# esquematico_drone.net
KiCad netlist of a schematic drawn in EAGLE
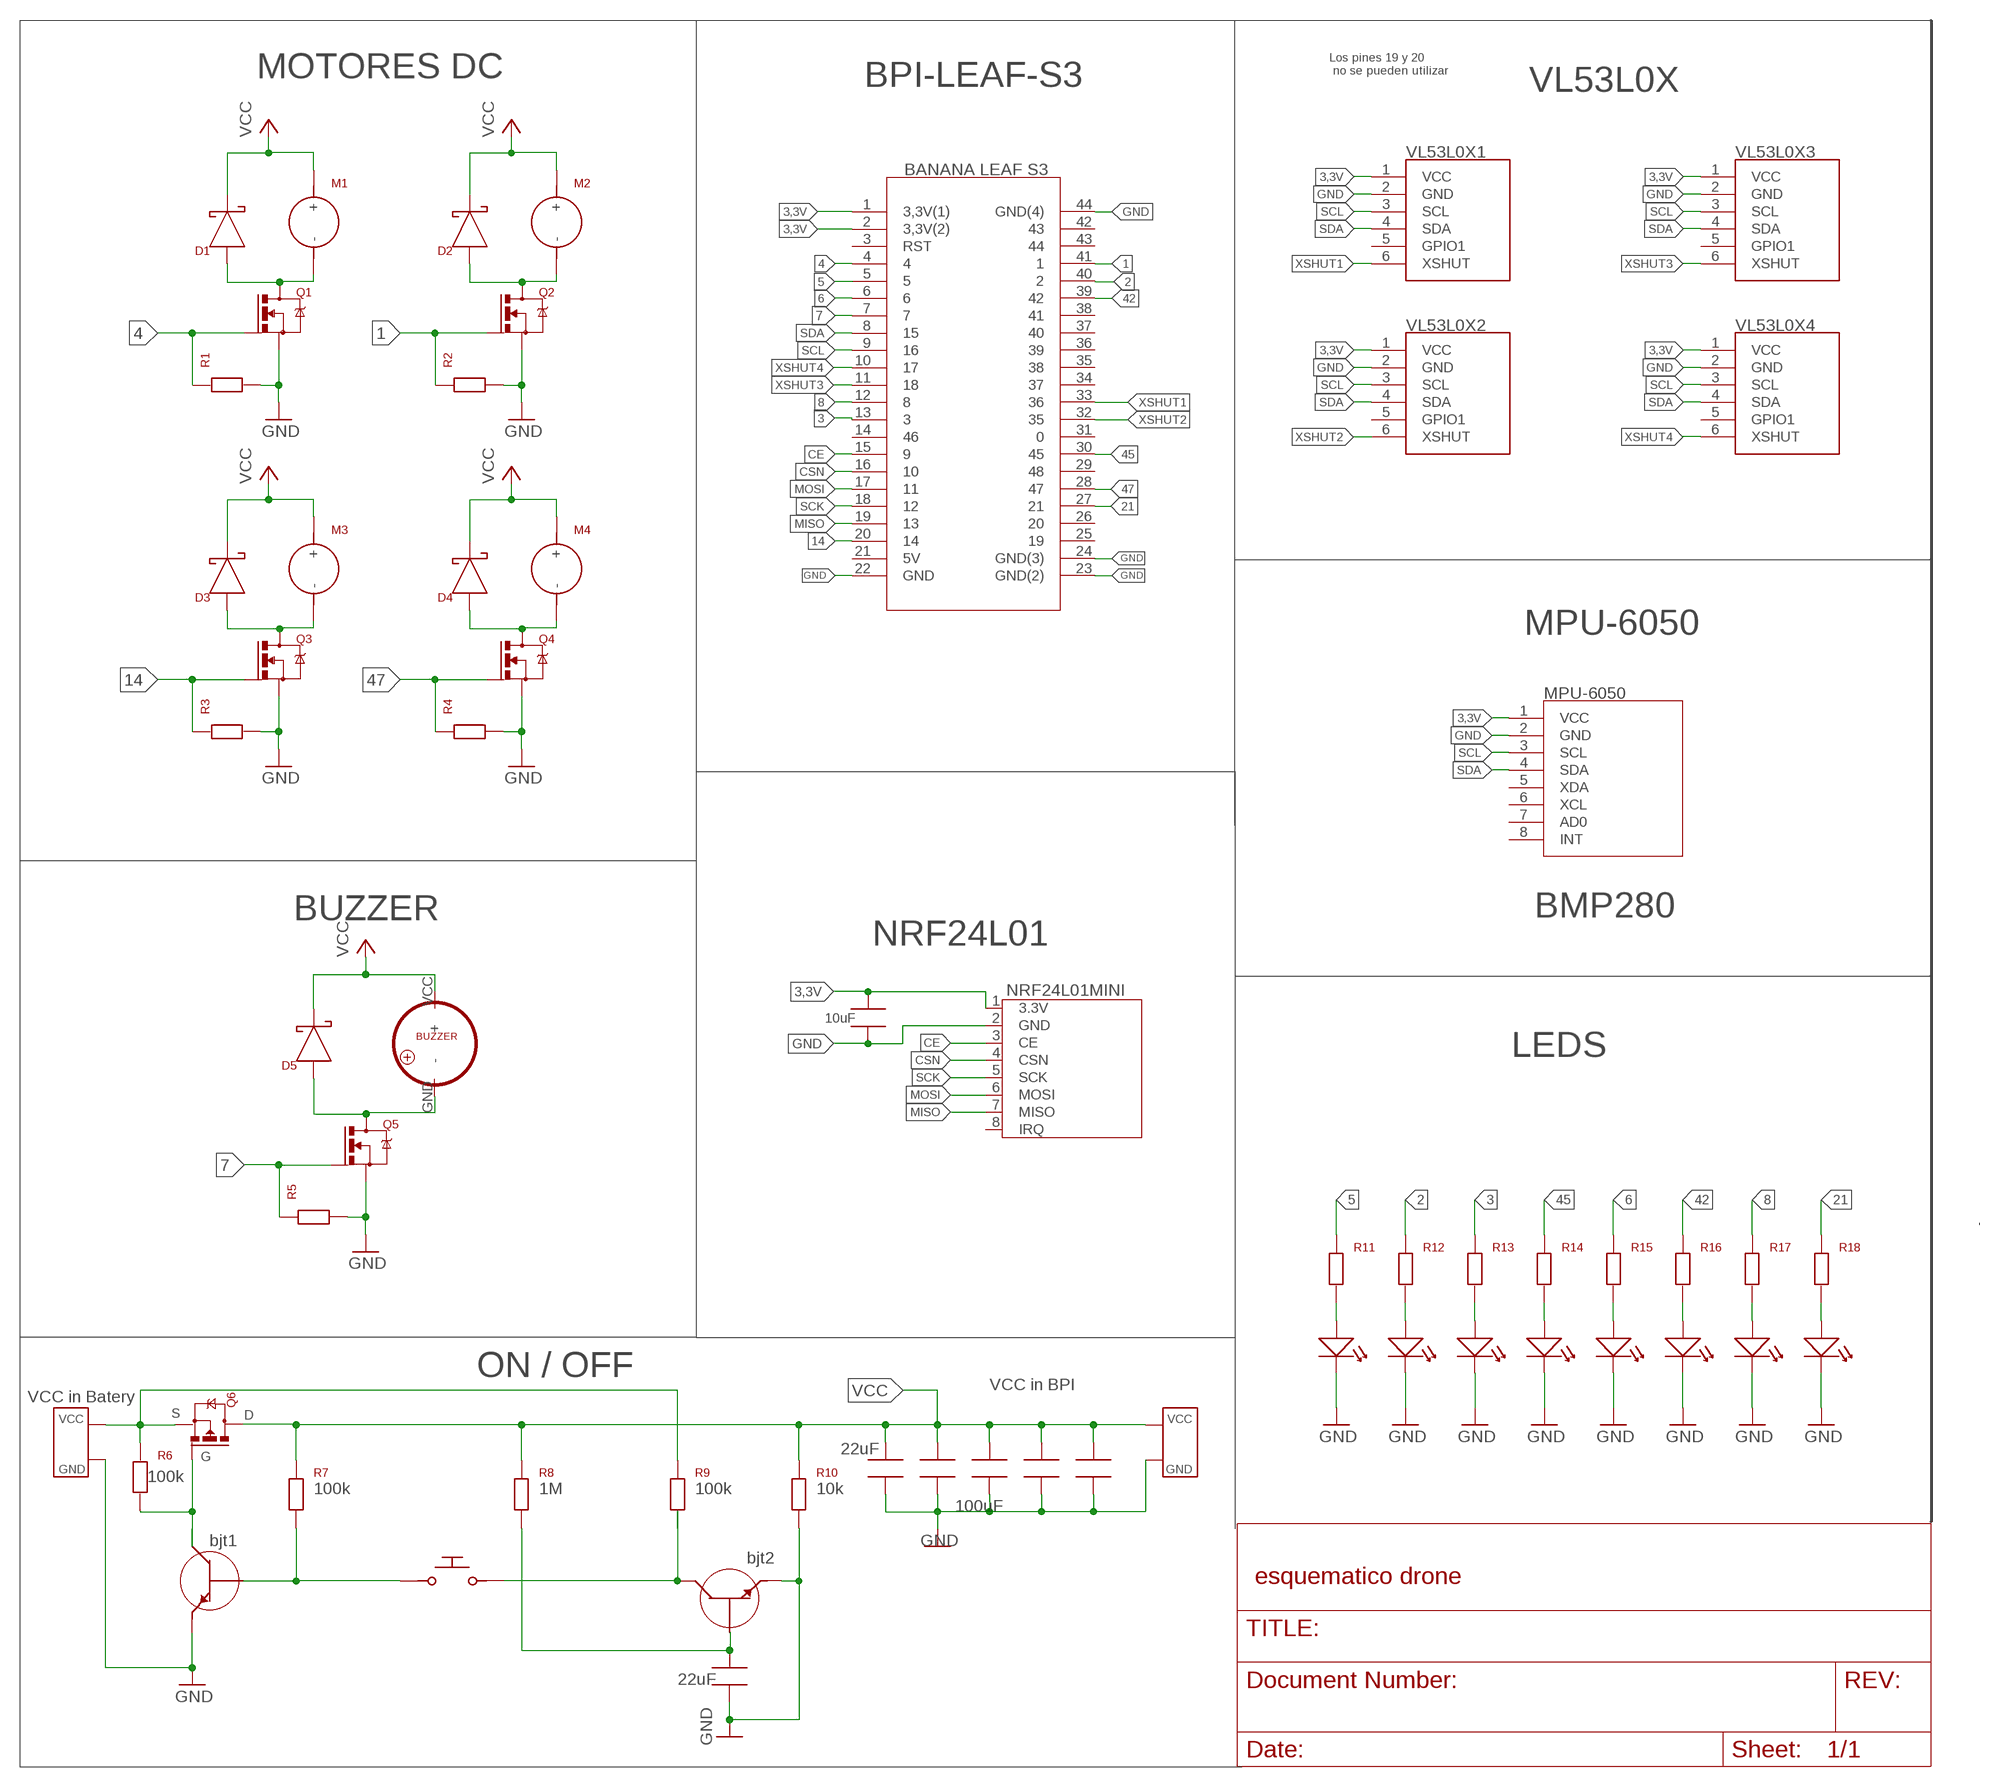
[diagram p0: schematic, sheet 1]

(export (version "E")
  (design (tool "Eeschema 10.0.6"))
  (components
    (comp (ref "BANANALEAFS1")
      (value "BANANALEAFS3")
      (footprint "eagle-import:BANANALEAF")
      (libsource (lib "eagle-import") (part "BANANALEAFS3"))
    )
    (comp (ref "BAT1")
      (value "BATBAT")
      (footprint "eagle-import:BAT")
      (libsource (lib "eagle-import") (part "BATBAT"))
    )
    (comp (ref "BAT2")
      (value "BATBAT")
      (footprint "eagle-import:BAT")
      (libsource (lib "eagle-import") (part "BATBAT"))
    )
    (comp (ref "BJT1")
      (value "MMBT3904")
      (footprint "eagle-import:MMBT3904")
      (libsource (lib "eagle-import") (part "MMBT3904"))
    )
    (comp (ref "BJT2")
      (value "MMBT3904")
      (footprint "eagle-import:MMBT3904")
      (libsource (lib "eagle-import") (part "MMBT3904"))
    )
    (comp (ref "C1")
      (value "100uF")
      (footprint "eagle-import:CAPACITOR-100UF")
      (libsource (lib "eagle-import") (part "CAPACITOR-100UFCAPACITOR"))
    )
    (comp (ref "C2")
      (value "CAPACITOR-22UF")
      (footprint "eagle-import:CAPACITOR-22UF")
      (libsource (lib "eagle-import") (part "CAPACITOR-22UF"))
    )
    (comp (ref "C3")
      (value "100uF")
      (footprint "eagle-import:CAPACITOR-100UF")
      (libsource (lib "eagle-import") (part "CAPACITOR-100UFCAPACITOR"))
    )
    (comp (ref "C4")
      (value "CAPACITOR-100UFCAPACITOR")
      (footprint "eagle-import:CAPACITOR-100UF")
      (libsource (lib "eagle-import") (part "CAPACITOR-100UFCAPACITOR"))
    )
    (comp (ref "C5")
      (value "CAPACITOR-100UFCAPACITOR")
      (footprint "eagle-import:CAPACITOR-100UF")
      (libsource (lib "eagle-import") (part "CAPACITOR-100UFCAPACITOR"))
    )
    (comp (ref "C6")
      (value "CAPACITOR-100UFCAPACITOR")
      (footprint "eagle-import:CAPACITOR-100UF")
      (libsource (lib "eagle-import") (part "CAPACITOR-100UFCAPACITOR"))
    )
    (comp (ref "C7")
      (value "CAPACITOR-22UF")
      (footprint "eagle-import:CAPACITOR-22UF")
      (libsource (lib "eagle-import") (part "CAPACITOR-22UF"))
    )
    (comp (ref "D1")
      (value "SS12")
      (footprint "eagle-import:SS12")
      (libsource (lib "eagle-import") (part "SS12"))
    )
    (comp (ref "D2")
      (value "SS12")
      (footprint "eagle-import:SS12")
      (libsource (lib "eagle-import") (part "SS12"))
    )
    (comp (ref "D3")
      (value "SS12")
      (footprint "eagle-import:SS12")
      (libsource (lib "eagle-import") (part "SS12"))
    )
    (comp (ref "D4")
      (value "SS12")
      (footprint "eagle-import:SS12")
      (libsource (lib "eagle-import") (part "SS12"))
    )
    (comp (ref "D5")
      (value "SS12")
      (footprint "eagle-import:SS12")
      (libsource (lib "eagle-import") (part "SS12"))
    )
    (comp (ref "LED1")
      (value "LEDS")
      (footprint "eagle-import:LEDS")
      (libsource (lib "eagle-import") (part "LEDS"))
    )
    (comp (ref "LED2")
      (value "LEDS")
      (footprint "eagle-import:LEDS")
      (libsource (lib "eagle-import") (part "LEDS"))
    )
    (comp (ref "LED3")
      (value "LEDS")
      (footprint "eagle-import:LEDS")
      (libsource (lib "eagle-import") (part "LEDS"))
    )
    (comp (ref "LED4")
      (value "LEDS")
      (footprint "eagle-import:LEDS")
      (libsource (lib "eagle-import") (part "LEDS"))
    )
    (comp (ref "LED5")
      (value "LEDS")
      (footprint "eagle-import:LEDS")
      (libsource (lib "eagle-import") (part "LEDS"))
    )
    (comp (ref "LED6")
      (value "LEDS")
      (footprint "eagle-import:LEDS")
      (libsource (lib "eagle-import") (part "LEDS"))
    )
    (comp (ref "LED7")
      (value "LEDS")
      (footprint "eagle-import:LEDS")
      (libsource (lib "eagle-import") (part "LEDS"))
    )
    (comp (ref "LED8")
      (value "LEDS")
      (footprint "eagle-import:LEDS")
      (libsource (lib "eagle-import") (part "LEDS"))
    )
    (comp (ref "M1")
      (value "MOTORM")
      (footprint "eagle-import:MOTOR")
      (libsource (lib "eagle-import") (part "MOTORM"))
    )
    (comp (ref "M2")
      (value "MOTORM")
      (footprint "eagle-import:MOTOR")
      (libsource (lib "eagle-import") (part "MOTORM"))
    )
    (comp (ref "M3")
      (value "MOTORM")
      (footprint "eagle-import:MOTOR")
      (libsource (lib "eagle-import") (part "MOTORM"))
    )
    (comp (ref "M4")
      (value "MOTORM")
      (footprint "eagle-import:MOTOR")
      (libsource (lib "eagle-import") (part "MOTORM"))
    )
    (comp (ref "MPU1")
      (value "MPU6050MPU6050")
      (footprint "eagle-import:MPU6050")
      (libsource (lib "eagle-import") (part "MPU6050MPU6050"))
    )
    (comp (ref "NRF24L1")
      (value "NRF24L01MINI")
      (footprint "eagle-import:NRF24L01MINI")
      (libsource (lib "eagle-import") (part "NRF24L01MINI"))
    )
    (comp (ref "P1")
      (value "PULSADOR")
      (footprint "eagle-import:PULSADOR")
      (libsource (lib "eagle-import") (part "PULSADOR"))
    )
    (comp (ref "Q1")
      (value "SI2302")
      (footprint "eagle-import:SI2302")
      (libsource (lib "eagle-import") (part "SI2302"))
    )
    (comp (ref "Q2")
      (value "SI2302")
      (footprint "eagle-import:SI2302")
      (libsource (lib "eagle-import") (part "SI2302"))
    )
    (comp (ref "Q3")
      (value "SI2302")
      (footprint "eagle-import:SI2302")
      (libsource (lib "eagle-import") (part "SI2302"))
    )
    (comp (ref "Q4")
      (value "SI2302")
      (footprint "eagle-import:SI2302")
      (libsource (lib "eagle-import") (part "SI2302"))
    )
    (comp (ref "Q5")
      (value "SI2302")
      (footprint "eagle-import:SI2302")
      (libsource (lib "eagle-import") (part "SI2302"))
    )
    (comp (ref "Q6")
      (value "SI2301SI2301")
      (footprint "eagle-import:SI2301")
      (libsource (lib "eagle-import") (part "SI2301SI2301"))
    )
    (comp (ref "R1")
      (value "RESISTOR-0805")
      (footprint "eagle-import:RESISTOR-0805")
      (libsource (lib "eagle-import") (part "RESISTOR-0805"))
    )
    (comp (ref "R2")
      (value "RESISTOR-0805")
      (footprint "eagle-import:RESISTOR-0805")
      (libsource (lib "eagle-import") (part "RESISTOR-0805"))
    )
    (comp (ref "R3")
      (value "RESISTOR-0805")
      (footprint "eagle-import:RESISTOR-0805")
      (libsource (lib "eagle-import") (part "RESISTOR-0805"))
    )
    (comp (ref "R4")
      (value "RESISTOR-0805")
      (footprint "eagle-import:RESISTOR-0805")
      (libsource (lib "eagle-import") (part "RESISTOR-0805"))
    )
    (comp (ref "R5")
      (value "RESISTOR-0805")
      (footprint "eagle-import:RESISTOR-0805")
      (libsource (lib "eagle-import") (part "RESISTOR-0805"))
    )
    (comp (ref "R6")
      (value "RESISTOR-0805")
      (footprint "eagle-import:RESISTOR-0805")
      (libsource (lib "eagle-import") (part "RESISTOR-0805"))
    )
    (comp (ref "R7")
      (value "RESISTOR-0805")
      (footprint "eagle-import:RESISTOR-0805")
      (libsource (lib "eagle-import") (part "RESISTOR-0805"))
    )
    (comp (ref "R8")
      (value "RESISTOR-0805")
      (footprint "eagle-import:RESISTOR-0805")
      (libsource (lib "eagle-import") (part "RESISTOR-0805"))
    )
    (comp (ref "R9")
      (value "RESISTOR-0805")
      (footprint "eagle-import:RESISTOR-0805")
      (libsource (lib "eagle-import") (part "RESISTOR-0805"))
    )
    (comp (ref "R10")
      (value "RESISTOR-0805")
      (footprint "eagle-import:RESISTOR-0805")
      (libsource (lib "eagle-import") (part "RESISTOR-0805"))
    )
    (comp (ref "R11")
      (value "RESISTOR-0805")
      (footprint "eagle-import:RESISTOR-0805")
      (libsource (lib "eagle-import") (part "RESISTOR-0805"))
    )
    (comp (ref "R12")
      (value "RESISTOR-0805")
      (footprint "eagle-import:RESISTOR-0805")
      (libsource (lib "eagle-import") (part "RESISTOR-0805"))
    )
    (comp (ref "R13")
      (value "RESISTOR-0805")
      (footprint "eagle-import:RESISTOR-0805")
      (libsource (lib "eagle-import") (part "RESISTOR-0805"))
    )
    (comp (ref "R14")
      (value "RESISTOR-0805")
      (footprint "eagle-import:RESISTOR-0805")
      (libsource (lib "eagle-import") (part "RESISTOR-0805"))
    )
    (comp (ref "R15")
      (value "RESISTOR-0805")
      (footprint "eagle-import:RESISTOR-0805")
      (libsource (lib "eagle-import") (part "RESISTOR-0805"))
    )
    (comp (ref "R16")
      (value "RESISTOR-0805")
      (footprint "eagle-import:RESISTOR-0805")
      (libsource (lib "eagle-import") (part "RESISTOR-0805"))
    )
    (comp (ref "R17")
      (value "RESISTOR-0805")
      (footprint "eagle-import:RESISTOR-0805")
      (libsource (lib "eagle-import") (part "RESISTOR-0805"))
    )
    (comp (ref "R18")
      (value "RESISTOR-0805")
      (footprint "eagle-import:RESISTOR-0805")
      (libsource (lib "eagle-import") (part "RESISTOR-0805"))
    )
    (comp (ref "U$2")
      (value "BUZZER")
      (footprint "eagle-import:BUZZER")
      (libsource (lib "eagle-import") (part "BUZZER"))
    )
    (comp (ref "VL53L0X1")
      (value "VL53L0X")
      (footprint "eagle-import:VL53L0X")
      (libsource (lib "eagle-import") (part "VL53L0X"))
    )
    (comp (ref "VL53L0X2")
      (value "VL53L0X")
      (footprint "eagle-import:VL53L0X")
      (libsource (lib "eagle-import") (part "VL53L0X"))
    )
    (comp (ref "VL53L0X3")
      (value "VL53L0X")
      (footprint "eagle-import:VL53L0X")
      (libsource (lib "eagle-import") (part "VL53L0X"))
    )
    (comp (ref "VL53L0X4")
      (value "VL53L0X")
      (footprint "eagle-import:VL53L0X")
      (libsource (lib "eagle-import") (part "VL53L0X"))
    )
  )
  (nets
    (net (code "1") (name "1") (class "Default")
      (node (ref "BANANALEAFS1") (pin "41") (pinfunction "1_41") (pintype "bidirectional"))
      (node (ref "Q2") (pin "G") (pinfunction "G_G") (pintype "bidirectional"))
      (node (ref "R2") (pin "S1") (pinfunction "P$1_S1") (pintype "bidirectional"))
    )
    (net (code "2") (name "2") (class "Default")
      (node (ref "BANANALEAFS1") (pin "40") (pinfunction "2_40") (pintype "bidirectional"))
      (node (ref "R12") (pin "S1") (pinfunction "P$1_S1") (pintype "bidirectional"))
    )
    (net (code "3") (name "3") (class "Default")
      (node (ref "BANANALEAFS1") (pin "13") (pinfunction "3_13") (pintype "bidirectional"))
      (node (ref "R13") (pin "S1") (pinfunction "P$1_S1") (pintype "bidirectional"))
    )
    (net (code "4") (name "3,3V") (class "Default")
      (node (ref "BANANALEAFS1") (pin "1") (pinfunction "3,3V(1)_1") (pintype "bidirectional"))
      (node (ref "BANANALEAFS1") (pin "2") (pinfunction "3,3V(2)_2") (pintype "bidirectional"))
      (node (ref "C7") (pin "S1") (pinfunction "C1_S1") (pintype "bidirectional"))
      (node (ref "MPU1") (pin "1") (pinfunction "VCC_1") (pintype "bidirectional"))
      (node (ref "NRF24L1") (pin "1") (pinfunction "3.3V_1") (pintype "bidirectional"))
      (node (ref "VL53L0X1") (pin "1") (pinfunction "VCC_1") (pintype "bidirectional"))
      (node (ref "VL53L0X2") (pin "1") (pinfunction "VCC_1") (pintype "bidirectional"))
      (node (ref "VL53L0X3") (pin "1") (pinfunction "VCC_1") (pintype "bidirectional"))
      (node (ref "VL53L0X4") (pin "1") (pinfunction "VCC_1") (pintype "bidirectional"))
    )
    (net (code "5") (name "4") (class "Default")
      (node (ref "BANANALEAFS1") (pin "4") (pinfunction "4_4") (pintype "bidirectional"))
      (node (ref "Q1") (pin "G") (pinfunction "G_G") (pintype "bidirectional"))
      (node (ref "R1") (pin "S1") (pinfunction "P$1_S1") (pintype "bidirectional"))
    )
    (net (code "6") (name "5") (class "Default")
      (node (ref "BANANALEAFS1") (pin "5") (pinfunction "5_5") (pintype "bidirectional"))
      (node (ref "R11") (pin "S1") (pinfunction "P$1_S1") (pintype "bidirectional"))
    )
    (net (code "7") (name "6") (class "Default")
      (node (ref "BANANALEAFS1") (pin "6") (pinfunction "6_6") (pintype "bidirectional"))
      (node (ref "R15") (pin "S1") (pinfunction "P$1_S1") (pintype "bidirectional"))
    )
    (net (code "8") (name "7") (class "Default")
      (node (ref "BANANALEAFS1") (pin "7") (pinfunction "7_7") (pintype "bidirectional"))
      (node (ref "Q5") (pin "G") (pinfunction "G_G") (pintype "bidirectional"))
      (node (ref "R5") (pin "S1") (pinfunction "P$1_S1") (pintype "bidirectional"))
    )
    (net (code "9") (name "8") (class "Default")
      (node (ref "BANANALEAFS1") (pin "12") (pinfunction "8_12") (pintype "bidirectional"))
      (node (ref "R17") (pin "S1") (pinfunction "P$1_S1") (pintype "bidirectional"))
    )
    (net (code "10") (name "14") (class "Default")
      (node (ref "BANANALEAFS1") (pin "20") (pinfunction "14_20") (pintype "bidirectional"))
      (node (ref "Q3") (pin "G") (pinfunction "G_G") (pintype "bidirectional"))
      (node (ref "R3") (pin "S1") (pinfunction "P$1_S1") (pintype "bidirectional"))
    )
    (net (code "11") (name "21") (class "Default")
      (node (ref "BANANALEAFS1") (pin "27") (pinfunction "21_27") (pintype "bidirectional"))
      (node (ref "R18") (pin "S1") (pinfunction "P$1_S1") (pintype "bidirectional"))
    )
    (net (code "12") (name "42") (class "Default")
      (node (ref "BANANALEAFS1") (pin "39") (pinfunction "42_39") (pintype "bidirectional"))
      (node (ref "R16") (pin "S1") (pinfunction "P$1_S1") (pintype "bidirectional"))
    )
    (net (code "13") (name "45") (class "Default")
      (node (ref "BANANALEAFS1") (pin "30") (pinfunction "45_30") (pintype "bidirectional"))
      (node (ref "R14") (pin "S1") (pinfunction "P$1_S1") (pintype "bidirectional"))
    )
    (net (code "14") (name "47") (class "Default")
      (node (ref "BANANALEAFS1") (pin "28") (pinfunction "47_28") (pintype "bidirectional"))
      (node (ref "Q4") (pin "G") (pinfunction "G_G") (pintype "bidirectional"))
      (node (ref "R4") (pin "S1") (pinfunction "P$1_S1") (pintype "bidirectional"))
    )
    (net (code "15") (name "CE") (class "Default")
      (node (ref "BANANALEAFS1") (pin "15") (pinfunction "9_15") (pintype "bidirectional"))
      (node (ref "NRF24L1") (pin "3") (pinfunction "CE_3") (pintype "bidirectional"))
    )
    (net (code "16") (name "CSN") (class "Default")
      (node (ref "BANANALEAFS1") (pin "16") (pinfunction "10_16") (pintype "bidirectional"))
      (node (ref "NRF24L1") (pin "4") (pinfunction "CSN_4") (pintype "bidirectional"))
    )
    (net (code "17") (name "GND") (class "Default")
      (node (ref "BANANALEAFS1") (pin "22") (pinfunction "GND_22") (pintype "bidirectional"))
      (node (ref "BANANALEAFS1") (pin "23") (pinfunction "GND(2)_23") (pintype "bidirectional"))
      (node (ref "BANANALEAFS1") (pin "24") (pinfunction "GND(3)_24") (pintype "bidirectional"))
      (node (ref "BANANALEAFS1") (pin "44") (pinfunction "GND(4)_44") (pintype "bidirectional"))
      (node (ref "BAT1") (pin "GND") (pinfunction "GND_GND") (pintype "bidirectional"))
      (node (ref "BAT2") (pin "GND") (pinfunction "GND_GND") (pintype "bidirectional"))
      (node (ref "BJT1") (pin "E") (pinfunction "E_E") (pintype "bidirectional"))
      (node (ref "BJT2") (pin "E") (pinfunction "E_E") (pintype "bidirectional"))
      (node (ref "C1") (pin "C2") (pinfunction "C2_C2") (pintype "bidirectional"))
      (node (ref "C2") (pin "S2") (pinfunction "C2_S2") (pintype "bidirectional"))
      (node (ref "C3") (pin "C2") (pinfunction "C2_C2") (pintype "bidirectional"))
      (node (ref "C4") (pin "C2") (pinfunction "C2_C2") (pintype "bidirectional"))
      (node (ref "C5") (pin "C2") (pinfunction "C2_C2") (pintype "bidirectional"))
      (node (ref "C6") (pin "C2") (pinfunction "C2_C2") (pintype "bidirectional"))
      (node (ref "C7") (pin "S2") (pinfunction "C2_S2") (pintype "bidirectional"))
      (node (ref "LED1") (pin "C") (pinfunction "C_C") (pintype "bidirectional"))
      (node (ref "LED2") (pin "C") (pinfunction "C_C") (pintype "bidirectional"))
      (node (ref "LED3") (pin "C") (pinfunction "C_C") (pintype "bidirectional"))
      (node (ref "LED4") (pin "C") (pinfunction "C_C") (pintype "bidirectional"))
      (node (ref "LED5") (pin "C") (pinfunction "C_C") (pintype "bidirectional"))
      (node (ref "LED6") (pin "C") (pinfunction "C_C") (pintype "bidirectional"))
      (node (ref "LED7") (pin "C") (pinfunction "C_C") (pintype "bidirectional"))
      (node (ref "LED8") (pin "C") (pinfunction "C_C") (pintype "bidirectional"))
      (node (ref "MPU1") (pin "2") (pinfunction "GND_2") (pintype "bidirectional"))
      (node (ref "NRF24L1") (pin "2") (pinfunction "GND_2") (pintype "bidirectional"))
      (node (ref "Q1") (pin "S") (pinfunction "S_S") (pintype "bidirectional"))
      (node (ref "Q2") (pin "S") (pinfunction "S_S") (pintype "bidirectional"))
      (node (ref "Q3") (pin "S") (pinfunction "S_S") (pintype "bidirectional"))
      (node (ref "Q4") (pin "S") (pinfunction "S_S") (pintype "bidirectional"))
      (node (ref "Q5") (pin "S") (pinfunction "S_S") (pintype "bidirectional"))
      (node (ref "R1") (pin "S2") (pinfunction "P$2_S2") (pintype "bidirectional"))
      (node (ref "R10") (pin "S2") (pinfunction "P$2_S2") (pintype "bidirectional"))
      (node (ref "R2") (pin "S2") (pinfunction "P$2_S2") (pintype "bidirectional"))
      (node (ref "R3") (pin "S2") (pinfunction "P$2_S2") (pintype "bidirectional"))
      (node (ref "R4") (pin "S2") (pinfunction "P$2_S2") (pintype "bidirectional"))
      (node (ref "R5") (pin "S2") (pinfunction "P$2_S2") (pintype "bidirectional"))
      (node (ref "VL53L0X1") (pin "2") (pinfunction "GND_2") (pintype "bidirectional"))
      (node (ref "VL53L0X2") (pin "2") (pinfunction "GND_2") (pintype "bidirectional"))
      (node (ref "VL53L0X3") (pin "2") (pinfunction "GND_2") (pintype "bidirectional"))
      (node (ref "VL53L0X4") (pin "2") (pinfunction "GND_2") (pintype "bidirectional"))
    )
    (net (code "18") (name "MISO") (class "Default")
      (node (ref "BANANALEAFS1") (pin "19") (pinfunction "13_19") (pintype "bidirectional"))
      (node (ref "NRF24L1") (pin "7") (pinfunction "MISO_7") (pintype "bidirectional"))
    )
    (net (code "19") (name "MOSI") (class "Default")
      (node (ref "BANANALEAFS1") (pin "17") (pinfunction "11_17") (pintype "bidirectional"))
      (node (ref "NRF24L1") (pin "6") (pinfunction "MOSI_6") (pintype "bidirectional"))
    )
    (net (code "20") (name "Net-(C2-C1)") (class "Default")
      (node (ref "BJT2") (pin "B") (pinfunction "B_B") (pintype "bidirectional"))
      (node (ref "C2") (pin "S1") (pinfunction "C1_S1") (pintype "bidirectional"))
      (node (ref "R8") (pin "S2") (pinfunction "P$2_S2") (pintype "bidirectional"))
    )
    (net (code "21") (name "Net-(D1-PadA)") (class "Default")
      (node (ref "D1") (pin "A") (pinfunction "A_A") (pintype "bidirectional"))
      (node (ref "M1") (pin "-") (pinfunction "-_-") (pintype "bidirectional"))
      (node (ref "Q1") (pin "D") (pinfunction "D_D") (pintype "bidirectional"))
    )
    (net (code "22") (name "Net-(D2-PadA)") (class "Default")
      (node (ref "D2") (pin "A") (pinfunction "A_A") (pintype "bidirectional"))
      (node (ref "M2") (pin "-") (pinfunction "-_-") (pintype "bidirectional"))
      (node (ref "Q2") (pin "D") (pinfunction "D_D") (pintype "bidirectional"))
    )
    (net (code "23") (name "Net-(D3-PadA)") (class "Default")
      (node (ref "D3") (pin "A") (pinfunction "A_A") (pintype "bidirectional"))
      (node (ref "M3") (pin "-") (pinfunction "-_-") (pintype "bidirectional"))
      (node (ref "Q3") (pin "D") (pinfunction "D_D") (pintype "bidirectional"))
    )
    (net (code "24") (name "Net-(D4-PadA)") (class "Default")
      (node (ref "D4") (pin "A") (pinfunction "A_A") (pintype "bidirectional"))
      (node (ref "M4") (pin "-") (pinfunction "-_-") (pintype "bidirectional"))
      (node (ref "Q4") (pin "D") (pinfunction "D_D") (pintype "bidirectional"))
    )
    (net (code "25") (name "Net-(P1-1)") (class "Default")
      (node (ref "BJT1") (pin "B") (pinfunction "B_B") (pintype "bidirectional"))
      (node (ref "P1") (pin "P1") (pinfunction "1_P1") (pintype "bidirectional"))
      (node (ref "R7") (pin "S2") (pinfunction "P$2_S2") (pintype "bidirectional"))
    )
    (net (code "26") (name "Net-(P1-2)") (class "Default")
      (node (ref "BJT2") (pin "C") (pinfunction "C_C") (pintype "bidirectional"))
      (node (ref "P1") (pin "P2") (pinfunction "2_P2") (pintype "bidirectional"))
      (node (ref "R9") (pin "S2") (pinfunction "P$2_S2") (pintype "bidirectional"))
    )
    (net (code "27") (name "Net-(R6-P$1)") (class "Default")
      (node (ref "BAT2") (pin "VCC") (pinfunction "VCC_VCC") (pintype "bidirectional"))
      (node (ref "Q6") (pin "S") (pinfunction "S_S") (pintype "bidirectional"))
      (node (ref "R6") (pin "S1") (pinfunction "P$1_S1") (pintype "bidirectional"))
      (node (ref "R9") (pin "S1") (pinfunction "P$1_S1") (pintype "bidirectional"))
    )
    (net (code "28") (name "Net-(R6-P$2)") (class "Default")
      (node (ref "BJT1") (pin "C") (pinfunction "C_C") (pintype "bidirectional"))
      (node (ref "Q6") (pin "G") (pinfunction "G_G") (pintype "bidirectional"))
      (node (ref "R6") (pin "S2") (pinfunction "P$2_S2") (pintype "bidirectional"))
    )
    (net (code "29") (name "Net-(R11-P$2)") (class "Default")
      (node (ref "LED1") (pin "A") (pinfunction "A_A") (pintype "bidirectional"))
      (node (ref "R11") (pin "S2") (pinfunction "P$2_S2") (pintype "bidirectional"))
    )
    (net (code "30") (name "Net-(R12-P$2)") (class "Default")
      (node (ref "LED2") (pin "A") (pinfunction "A_A") (pintype "bidirectional"))
      (node (ref "R12") (pin "S2") (pinfunction "P$2_S2") (pintype "bidirectional"))
    )
    (net (code "31") (name "Net-(R13-P$2)") (class "Default")
      (node (ref "LED3") (pin "A") (pinfunction "A_A") (pintype "bidirectional"))
      (node (ref "R13") (pin "S2") (pinfunction "P$2_S2") (pintype "bidirectional"))
    )
    (net (code "32") (name "Net-(R14-P$2)") (class "Default")
      (node (ref "LED4") (pin "A") (pinfunction "A_A") (pintype "bidirectional"))
      (node (ref "R14") (pin "S2") (pinfunction "P$2_S2") (pintype "bidirectional"))
    )
    (net (code "33") (name "Net-(R15-P$2)") (class "Default")
      (node (ref "LED5") (pin "A") (pinfunction "A_A") (pintype "bidirectional"))
      (node (ref "R15") (pin "S2") (pinfunction "P$2_S2") (pintype "bidirectional"))
    )
    (net (code "34") (name "Net-(R16-P$2)") (class "Default")
      (node (ref "LED6") (pin "A") (pinfunction "A_A") (pintype "bidirectional"))
      (node (ref "R16") (pin "S2") (pinfunction "P$2_S2") (pintype "bidirectional"))
    )
    (net (code "35") (name "Net-(R17-P$2)") (class "Default")
      (node (ref "LED7") (pin "A") (pinfunction "A_A") (pintype "bidirectional"))
      (node (ref "R17") (pin "S2") (pinfunction "P$2_S2") (pintype "bidirectional"))
    )
    (net (code "36") (name "Net-(R18-P$2)") (class "Default")
      (node (ref "LED8") (pin "A") (pinfunction "A_A") (pintype "bidirectional"))
      (node (ref "R18") (pin "S2") (pinfunction "P$2_S2") (pintype "bidirectional"))
    )
    (net (code "37") (name "Net-(U$2--)") (class "Default")
      (node (ref "D5") (pin "A") (pinfunction "A_A") (pintype "bidirectional"))
      (node (ref "Q5") (pin "D") (pinfunction "D_D") (pintype "bidirectional"))
      (node (ref "U$2") (pin "GND") (pinfunction "-_GND") (pintype "bidirectional"))
    )
    (net (code "38") (name "SCK") (class "Default")
      (node (ref "BANANALEAFS1") (pin "18") (pinfunction "12_18") (pintype "bidirectional"))
      (node (ref "NRF24L1") (pin "5") (pinfunction "SCK_5") (pintype "bidirectional"))
    )
    (net (code "39") (name "SCL") (class "Default")
      (node (ref "BANANALEAFS1") (pin "9") (pinfunction "16_9") (pintype "bidirectional"))
      (node (ref "MPU1") (pin "3") (pinfunction "SCL_3") (pintype "bidirectional"))
      (node (ref "VL53L0X1") (pin "3") (pinfunction "SCL_3") (pintype "bidirectional"))
      (node (ref "VL53L0X2") (pin "3") (pinfunction "SCL_3") (pintype "bidirectional"))
      (node (ref "VL53L0X3") (pin "3") (pinfunction "SCL_3") (pintype "bidirectional"))
      (node (ref "VL53L0X4") (pin "3") (pinfunction "SCL_3") (pintype "bidirectional"))
    )
    (net (code "40") (name "SDA") (class "Default")
      (node (ref "BANANALEAFS1") (pin "8") (pinfunction "15_8") (pintype "bidirectional"))
      (node (ref "MPU1") (pin "4") (pinfunction "SDA_4") (pintype "bidirectional"))
      (node (ref "VL53L0X1") (pin "4") (pinfunction "SDA_4") (pintype "bidirectional"))
      (node (ref "VL53L0X2") (pin "4") (pinfunction "SDA_4") (pintype "bidirectional"))
      (node (ref "VL53L0X3") (pin "4") (pinfunction "SDA_4") (pintype "bidirectional"))
      (node (ref "VL53L0X4") (pin "4") (pinfunction "SDA_4") (pintype "bidirectional"))
    )
    (net (code "41") (name "VCC") (class "Default")
      (node (ref "BAT1") (pin "VCC") (pinfunction "VCC_VCC") (pintype "bidirectional"))
      (node (ref "C1") (pin "C1") (pinfunction "C1_C1") (pintype "bidirectional"))
      (node (ref "C3") (pin "C1") (pinfunction "C1_C1") (pintype "bidirectional"))
      (node (ref "C4") (pin "C1") (pinfunction "C1_C1") (pintype "bidirectional"))
      (node (ref "C5") (pin "C1") (pinfunction "C1_C1") (pintype "bidirectional"))
      (node (ref "C6") (pin "C1") (pinfunction "C1_C1") (pintype "bidirectional"))
      (node (ref "D1") (pin "C") (pinfunction "C_C") (pintype "bidirectional"))
      (node (ref "D2") (pin "C") (pinfunction "C_C") (pintype "bidirectional"))
      (node (ref "D3") (pin "C") (pinfunction "C_C") (pintype "bidirectional"))
      (node (ref "D4") (pin "C") (pinfunction "C_C") (pintype "bidirectional"))
      (node (ref "D5") (pin "C") (pinfunction "C_C") (pintype "bidirectional"))
      (node (ref "M1") (pin "+") (pinfunction "+_+") (pintype "bidirectional"))
      (node (ref "M2") (pin "+") (pinfunction "+_+") (pintype "bidirectional"))
      (node (ref "M3") (pin "+") (pinfunction "+_+") (pintype "bidirectional"))
      (node (ref "M4") (pin "+") (pinfunction "+_+") (pintype "bidirectional"))
      (node (ref "Q6") (pin "D") (pinfunction "D_D") (pintype "bidirectional"))
      (node (ref "R10") (pin "S1") (pinfunction "P$1_S1") (pintype "bidirectional"))
      (node (ref "R7") (pin "S1") (pinfunction "P$1_S1") (pintype "bidirectional"))
      (node (ref "R8") (pin "S1") (pinfunction "P$1_S1") (pintype "bidirectional"))
      (node (ref "U$2") (pin "VCC") (pinfunction "+_VCC") (pintype "bidirectional"))
    )
    (net (code "42") (name "XSHUT1") (class "Default")
      (node (ref "BANANALEAFS1") (pin "33") (pinfunction "36_33") (pintype "bidirectional"))
      (node (ref "VL53L0X1") (pin "6") (pinfunction "XSHUT_6") (pintype "bidirectional"))
    )
    (net (code "43") (name "XSHUT2") (class "Default")
      (node (ref "BANANALEAFS1") (pin "32") (pinfunction "35_32") (pintype "bidirectional"))
      (node (ref "VL53L0X2") (pin "6") (pinfunction "XSHUT_6") (pintype "bidirectional"))
    )
    (net (code "44") (name "XSHUT3") (class "Default")
      (node (ref "BANANALEAFS1") (pin "11") (pinfunction "18_11") (pintype "bidirectional"))
      (node (ref "VL53L0X3") (pin "6") (pinfunction "XSHUT_6") (pintype "bidirectional"))
    )
    (net (code "45") (name "XSHUT4") (class "Default")
      (node (ref "BANANALEAFS1") (pin "10") (pinfunction "17_10") (pintype "bidirectional"))
      (node (ref "VL53L0X4") (pin "6") (pinfunction "XSHUT_6") (pintype "bidirectional"))
    )
    (net (code "46") (name "unconnected-(BANANALEAFS1-0-Pad31)") (class "Default")
      (node (ref "BANANALEAFS1") (pin "31") (pinfunction "0_31") (pintype "bidirectional"))
    )
    (net (code "47") (name "unconnected-(BANANALEAFS1-5V-Pad21)") (class "Default")
      (node (ref "BANANALEAFS1") (pin "21") (pinfunction "5V_21") (pintype "bidirectional"))
    )
    (net (code "48") (name "unconnected-(BANANALEAFS1-19-Pad25)") (class "Default")
      (node (ref "BANANALEAFS1") (pin "25") (pinfunction "19_25") (pintype "bidirectional"))
    )
    (net (code "49") (name "unconnected-(BANANALEAFS1-20-Pad26)") (class "Default")
      (node (ref "BANANALEAFS1") (pin "26") (pinfunction "20_26") (pintype "bidirectional"))
    )
    (net (code "50") (name "unconnected-(BANANALEAFS1-37-Pad34)") (class "Default")
      (node (ref "BANANALEAFS1") (pin "34") (pinfunction "37_34") (pintype "bidirectional"))
    )
    (net (code "51") (name "unconnected-(BANANALEAFS1-38-Pad35)") (class "Default")
      (node (ref "BANANALEAFS1") (pin "35") (pinfunction "38_35") (pintype "bidirectional"))
    )
    (net (code "52") (name "unconnected-(BANANALEAFS1-39-Pad36)") (class "Default")
      (node (ref "BANANALEAFS1") (pin "36") (pinfunction "39_36") (pintype "bidirectional"))
    )
    (net (code "53") (name "unconnected-(BANANALEAFS1-40-Pad37)") (class "Default")
      (node (ref "BANANALEAFS1") (pin "37") (pinfunction "40_37") (pintype "bidirectional"))
    )
    (net (code "54") (name "unconnected-(BANANALEAFS1-41-Pad38)") (class "Default")
      (node (ref "BANANALEAFS1") (pin "38") (pinfunction "41_38") (pintype "bidirectional"))
    )
    (net (code "55") (name "unconnected-(BANANALEAFS1-43-Pad42)") (class "Default")
      (node (ref "BANANALEAFS1") (pin "42") (pinfunction "43_42") (pintype "bidirectional"))
    )
    (net (code "56") (name "unconnected-(BANANALEAFS1-44-Pad43)") (class "Default")
      (node (ref "BANANALEAFS1") (pin "43") (pinfunction "44_43") (pintype "bidirectional"))
    )
    (net (code "57") (name "unconnected-(BANANALEAFS1-46-Pad14)") (class "Default")
      (node (ref "BANANALEAFS1") (pin "14") (pinfunction "46_14") (pintype "bidirectional"))
    )
    (net (code "58") (name "unconnected-(BANANALEAFS1-48-Pad29)") (class "Default")
      (node (ref "BANANALEAFS1") (pin "29") (pinfunction "48_29") (pintype "bidirectional"))
    )
    (net (code "59") (name "unconnected-(BANANALEAFS1-RST-Pad3)") (class "Default")
      (node (ref "BANANALEAFS1") (pin "3") (pinfunction "RST_3") (pintype "bidirectional"))
    )
    (net (code "60") (name "unconnected-(MPU1-AD0-Pad7)") (class "Default")
      (node (ref "MPU1") (pin "7") (pinfunction "AD0_7") (pintype "bidirectional"))
    )
    (net (code "61") (name "unconnected-(MPU1-INT-Pad8)") (class "Default")
      (node (ref "MPU1") (pin "8") (pinfunction "INT_8") (pintype "bidirectional"))
    )
    (net (code "62") (name "unconnected-(MPU1-XCL-Pad6)") (class "Default")
      (node (ref "MPU1") (pin "6") (pinfunction "XCL_6") (pintype "bidirectional"))
    )
    (net (code "63") (name "unconnected-(MPU1-XDA-Pad5)") (class "Default")
      (node (ref "MPU1") (pin "5") (pinfunction "XDA_5") (pintype "bidirectional"))
    )
    (net (code "64") (name "unconnected-(NRF24L1-IRQ-Pad8)") (class "Default")
      (node (ref "NRF24L1") (pin "8") (pinfunction "IRQ_8") (pintype "bidirectional"))
    )
    (net (code "65") (name "unconnected-(VL53L0X1-GPIO1-Pad5)") (class "Default")
      (node (ref "VL53L0X1") (pin "5") (pinfunction "GPIO1_5") (pintype "bidirectional"))
    )
    (net (code "66") (name "unconnected-(VL53L0X2-GPIO1-Pad5)") (class "Default")
      (node (ref "VL53L0X2") (pin "5") (pinfunction "GPIO1_5") (pintype "bidirectional"))
    )
    (net (code "67") (name "unconnected-(VL53L0X3-GPIO1-Pad5)") (class "Default")
      (node (ref "VL53L0X3") (pin "5") (pinfunction "GPIO1_5") (pintype "bidirectional"))
    )
    (net (code "68") (name "unconnected-(VL53L0X4-GPIO1-Pad5)") (class "Default")
      (node (ref "VL53L0X4") (pin "5") (pinfunction "GPIO1_5") (pintype "bidirectional"))
    )
  )
)
